# DS1302.net
KiCad netlist of a schematic drawn in Altium Designer
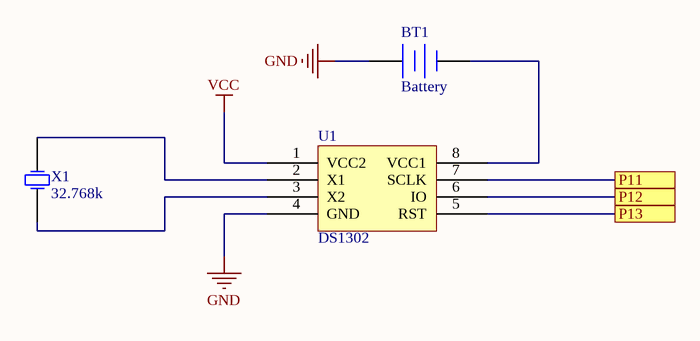
[diagram p0: DS1302.SchDoc]

(export (version "E")
  (design (tool "Eeschema 10.0.6"))
  (components
    (comp (ref "BT1") (value "Battery") (footprint "BT") (libsource (lib "TEST2024") (part "Battery")))
    (comp (ref "U1") (value "DS1302") (footprint "DIP8") (libsource (lib "TEST2024") (part "DS1302")))
    (comp (ref "X1") (value "32.768k") (footprint "XTAL2") (libsource (lib "TEST2024") (part "XTAL_2")))
  )
  (nets
    (net (code "1") (name "/P11") (class "Default")
      (node (ref "U1") (pin "7") (pinfunction "SCLK_7") (pintype "passive"))
    )
    (net (code "2") (name "/P12") (class "Default")
      (node (ref "U1") (pin "6") (pinfunction "IO_6") (pintype "passive"))
    )
    (net (code "3") (name "/P13") (class "Default")
      (node (ref "U1") (pin "5") (pinfunction "RST_5") (pintype "passive"))
    )
    (net (code "4") (name "GND") (class "Default")
      (node (ref "BT1") (pin "1") (pinfunction "+_1") (pintype "passive"))
      (node (ref "U1") (pin "4") (pinfunction "GND_4") (pintype "passive"))
    )
    (net (code "5") (name "Net-(BT1--)") (class "Default")
      (node (ref "BT1") (pin "2") (pinfunction "-_2") (pintype "passive"))
      (node (ref "U1") (pin "8") (pinfunction "VCC1_8") (pintype "passive"))
    )
    (net (code "6") (name "Net-(U1-X1)") (class "Default")
      (node (ref "U1") (pin "2") (pinfunction "X1_2") (pintype "passive"))
      (node (ref "X1") (pin "2") (pinfunction "OSC2_2") (pintype "passive"))
    )
    (net (code "7") (name "Net-(U1-X2)") (class "Default")
      (node (ref "U1") (pin "3") (pinfunction "X2_3") (pintype "passive"))
      (node (ref "X1") (pin "1") (pinfunction "OSC1_1") (pintype "passive"))
    )
    (net (code "8") (name "VCC") (class "Default")
      (node (ref "U1") (pin "1") (pinfunction "VCC2_1") (pintype "passive"))
    )
  )
)
